# alertButton.net
KiCad netlist of a schematic drawn in Altium Designer
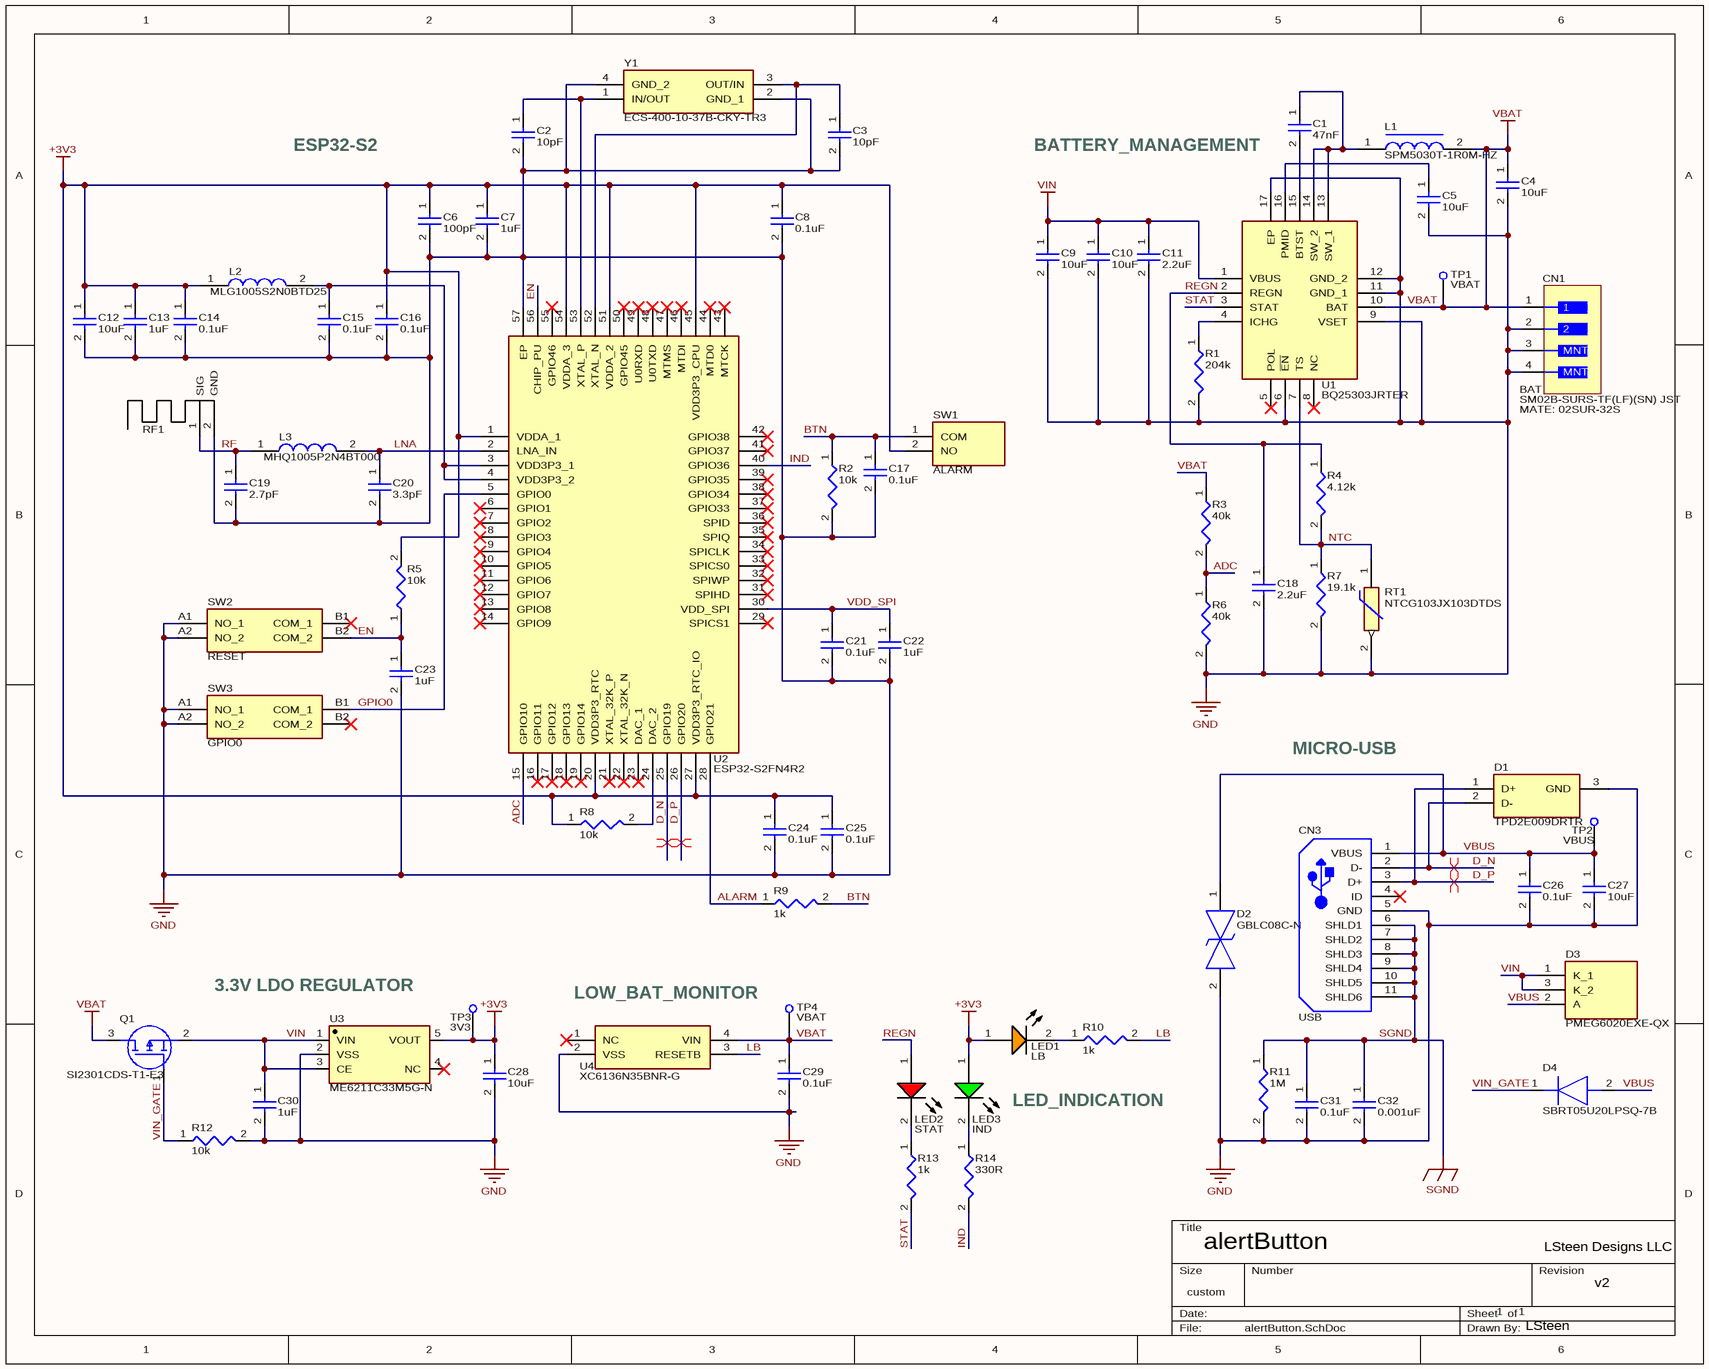
[diagram p0: alertButton.SchDoc]

(export (version "E")
  (design (tool "Eeschema 10.0.6"))
  (components
    (comp (ref "C1")
      (value "47nF")
      (footprint "SamacSys:CAPC1005X55N")
      (description "C0402")
      (libsource (lib "SamacSys") (part "C0402"))
    )
    (comp (ref "C2")
      (value "10pF")
      (footprint "SamacSys:CAPC1005X55N")
      (description "C0402")
      (libsource (lib "SamacSys") (part "C0402"))
    )
    (comp (ref "C3")
      (value "10pF")
      (footprint "SamacSys:CAPC1005X55N")
      (description "C0402")
      (libsource (lib "SamacSys") (part "C0402"))
    )
    (comp (ref "C4")
      (value "10uF")
      (footprint "SamacSys:CAPC1608X90N")
      (description "C0603")
      (libsource (lib "SamacSys") (part "C0603"))
    )
    (comp (ref "C5")
      (value "10uF")
      (footprint "SamacSys:CAPC1608X90N")
      (description "C0603")
      (libsource (lib "SamacSys") (part "C0603"))
    )
    (comp (ref "C6")
      (value "100pF")
      (footprint "SamacSys:CAPC1005X55N")
      (description "C0402")
      (libsource (lib "SamacSys") (part "C0402"))
    )
    (comp (ref "C7")
      (value "1uF")
      (footprint "SamacSys:CAPC1005X55N")
      (description "C0402")
      (libsource (lib "SamacSys") (part "C0402"))
    )
    (comp (ref "C8")
      (value "0.1uF")
      (footprint "SamacSys:CAPC1005X55N")
      (description "C0402")
      (libsource (lib "SamacSys") (part "C0402"))
    )
    (comp (ref "C9")
      (value "10uF")
      (footprint "SamacSys:CAPC1608X90N")
      (description "C0603")
      (libsource (lib "SamacSys") (part "C0603"))
    )
    (comp (ref "C10")
      (value "10uF")
      (footprint "SamacSys:CAPC1608X90N")
      (description "C0603")
      (libsource (lib "SamacSys") (part "C0603"))
    )
    (comp (ref "C11")
      (value "2.2uF")
      (footprint "SamacSys:CAPC1005X55N")
      (description "C0402")
      (libsource (lib "SamacSys") (part "C0402"))
    )
    (comp (ref "C12")
      (value "10uF")
      (footprint "SamacSys:CAPC2012X140N")
      (description "C0805")
      (libsource (lib "SamacSys") (part "C0805"))
    )
    (comp (ref "C13")
      (value "1uF")
      (footprint "SamacSys:CAPC1005X55N")
      (description "C0402")
      (libsource (lib "SamacSys") (part "C0402"))
    )
    (comp (ref "C14")
      (value "0.1uF")
      (footprint "SamacSys:CAPC1005X55N")
      (description "C0402")
      (libsource (lib "SamacSys") (part "C0402"))
    )
    (comp (ref "C15")
      (value "0.1uF")
      (footprint "SamacSys:CAPC1005X55N")
      (description "C0402")
      (libsource (lib "SamacSys") (part "C0402"))
    )
    (comp (ref "C16")
      (value "0.1uF")
      (footprint "SamacSys:CAPC1005X55N")
      (description "C0402")
      (libsource (lib "SamacSys") (part "C0402"))
    )
    (comp (ref "C17")
      (value "0.1uF")
      (footprint "SamacSys:CAPC1005X55N")
      (description "C0402")
      (libsource (lib "SamacSys") (part "C0402"))
    )
    (comp (ref "C18")
      (value "2.2uF")
      (footprint "SamacSys:CAPC1005X55N")
      (description "C0402")
      (libsource (lib "SamacSys") (part "C0402"))
    )
    (comp (ref "C19")
      (value "2.7pF")
      (footprint "SamacSys:CAPC1005X56N")
      (description "C0402")
      (fields
        (field (name "MANUFACTURER_PART_NUMBER") "04023U2R7BAT2A")
        (field (name "MOUSER PART NUMBER") "581-04023U2.7B")
      )
      (libsource (lib "SamacSys") (part "04023U2R7BAT2A"))
    )
    (comp (ref "C20")
      (value "3.3pF")
      (footprint "SamacSys:CAPC1005X56N")
      (description "C0402")
      (fields (field (name "MANUFACTURER_PART_NUMBER") "04023A3R3CAT2A"))
      (libsource (lib "SamacSys") (part "04023A3R3CAT2A"))
    )
    (comp (ref "C21")
      (value "0.1uF")
      (footprint "SamacSys:CAPC1005X55N")
      (description "C0402")
      (libsource (lib "SamacSys") (part "C0402"))
    )
    (comp (ref "C22")
      (value "1uF")
      (footprint "SamacSys:CAPC1005X55N")
      (description "C0402")
      (libsource (lib "SamacSys") (part "C0402"))
    )
    (comp (ref "C23")
      (value "1uF")
      (footprint "SamacSys:CAPC1005X55N")
      (description "C0402")
      (libsource (lib "SamacSys") (part "C0402"))
    )
    (comp (ref "C24")
      (value "0.1uF")
      (footprint "SamacSys:CAPC1005X55N")
      (description "C0402")
      (libsource (lib "SamacSys") (part "C0402"))
    )
    (comp (ref "C25")
      (value "0.1uF")
      (footprint "SamacSys:CAPC1005X55N")
      (description "C0402")
      (libsource (lib "SamacSys") (part "C0402"))
    )
    (comp (ref "C26")
      (value "0.1uF")
      (footprint "SamacSys:CAPC1005X55N")
      (description "C0402")
      (libsource (lib "SamacSys") (part "C0402"))
    )
    (comp (ref "C27")
      (value "10uF")
      (footprint "SamacSys:CAPC1608X90N")
      (description "C0603")
      (libsource (lib "SamacSys") (part "C0603"))
    )
    (comp (ref "C28")
      (value "10uF")
      (footprint "SamacSys:CAPC1608X90N")
      (description "C0603")
      (libsource (lib "SamacSys") (part "C0603"))
    )
    (comp (ref "C29")
      (value "0.1uF")
      (footprint "SamacSys:CAPC1005X55N")
      (description "C0402")
      (libsource (lib "") (part "C0402_1"))
    )
    (comp (ref "C30")
      (value "1uF")
      (footprint "SamacSys:CAPC1005X55N")
      (description "C0402")
      (libsource (lib "SamacSys") (part "C0402"))
    )
    (comp (ref "C31")
      (value "0.1uF")
      (footprint "SamacSys:CAPC1005X55N")
      (description "C0402")
      (libsource (lib "SamacSys") (part "C0402"))
    )
    (comp (ref "C32")
      (value "0.001uF")
      (footprint "SamacSys:CAPC1005X55N")
      (description "C0402")
      (libsource (lib "SamacSys") (part "C0402"))
    )
    (comp (ref "CN1")
      (value "BAT")
      (footprint "SM02B-SURS-TF(LF)(SN)")
      (description "Connector")
      (fields
        (field (name "MANUFACTURER_PART_NUMBER") "SM02B-SURS-TF(LF)(SN)")
        (field (name "MOUSER PART NUMBER") "306-SM02B-SURS-TF(LF)(SN)")
      )
      (libsource (lib "Schlib1") (part "SM02B-SURS-TF(LF)(SN)"))
    )
    (comp (ref "CN3")
      (value "USB")
      (footprint "105017-0001")
      (description "Micro USB Connector")
      (fields
        (field (name "MANUFACTURER_PART_NUMBER") "105017-0001")
        (field (name "MOUSER PART NUMBER") "538-105017-0001")
      )
      (libsource (lib "SamacSys") (part "105017-0001"))
    )
    (comp (ref "D1")
      (value "TPD2E009DRTR")
      (footprint "SamacSys:SOTFL35P100X50-3N")
      (description "Integrated Circuit")
      (fields (field (name "MOUSER PART NUMBER") "595-TPD2E009DRTR"))
      (libsource (lib "SamacSys") (part "TPD2E009DRTR"))
    )
    (comp (ref "D2")
      (value "GBLC08C-N")
      (footprint "SOD-323_L1.8-W1.3-LS2.5-BI")
      (description "ESD DIODE-BI_LCSC#C314256")
      (libsource (lib "Schlib1") (part "GBLC08C-N"))
    )
    (comp (ref "D3")
      (value "PMEG6020EXE-QX")
      (footprint "SamacSys:PMEG6020EXEQX")
      (description "Schottky Diode")
      (libsource (lib "SamacSys") (part "PMEG6020EXE-QX"))
    )
    (comp (ref "D4")
      (value "SBRT05U20LPSQ-7B")
      (footprint "SamacSys:SBRT05U20LPSQ7B")
      (description "Diode")
      (fields (field (name "MOUSER PART NUMBER") "621-SBRT05U20LPSQ-7B"))
      (libsource (lib "SamacSys") (part "SBRT05U20LPSQ-7B"))
    )
    (comp (ref "L1")
      (value "SPM5030T-1R0M-HZ")
      (footprint "SamacSys:SPM5030")
      (description "Inductor (FeSi Core)")
      (fields (field (name "MOUSER PART NUMBER") "810-SPM5030T-1R0M-HZ"))
      (libsource (lib "SamacSys") (part "SPM5030T-1R0M-HZ"))
    )
    (comp (ref "L2")
      (value "MLG1005S2N0BTD25")
      (footprint "SamacSys:MLG1005")
      (description "Inductor")
      (fields (field (name "MOUSER PART NUMBER") "810-MLG1005S2N0BTD25"))
      (libsource (lib "SamacSys") (part "MLG1005S2N0BTD25"))
    )
    (comp (ref "L3")
      (value "MHQ1005P2N4BT000")
      (footprint "SamacSys:MHQ1005")
      (description "Inductor")
      (libsource (lib "SamacSys") (part "MHQ1005P2N4BT000"))
    )
    (comp (ref "LED1")
      (value "LB")
      (footprint "SM0402OC")
      (description "LED ORANGE")
      (fields
        (field (name "MANUFACTURER_PART_NUMBER") "SM0402OC")
        (field (name "MOUSER PART NUMBER") "749-SM0402OC")
      )
      (libsource (lib "SamacSys") (part "SM0402OC"))
    )
    (comp (ref "LED2")
      (value "STAT")
      (footprint "SamacSys:SM0402RC")
      (description "LED RED")
      (fields
        (field (name "MANUFACTURER_PART_NUMBER") "SM0402RC")
        (field (name "MOUSER PART NUMBER") "749-SM0402RC")
      )
      (libsource (lib "SamacSys") (part "SM0402RC"))
    )
    (comp (ref "LED3")
      (value "IND")
      (footprint "SamacSys:SM0402GC")
      (description "LED GREEN")
      (fields
        (field (name "MANUFACTURER_PART_NUMBER") "SM0402GC")
        (field (name "MOUSER PART NUMBER") "749-SM0402GC")
      )
      (libsource (lib "SamacSys") (part "SM0402GC"))
    )
    (comp (ref "Q1")
      (value "SI2301CDS-T1-E3")
      (footprint "SamacSys:SOT95P237X112-3N")
      (description "MOSFET (P-Channel)")
      (fields (field (name "MOUSER PART NUMBER") "781-SI2301CDS-E3"))
      (libsource (lib "SamacSys") (part "SI2301CDS-T1-E3"))
    )
    (comp (ref "R1")
      (value "204k")
      (footprint "SamacSys:ERA2AED122X")
      (description "R0402")
      (libsource (lib "SamacSys") (part "R0402"))
    )
    (comp (ref "R2")
      (value "10k")
      (footprint "SamacSys:ERA2AED122X")
      (description "R0402")
      (libsource (lib "SamacSys") (part "R0402"))
    )
    (comp (ref "R3")
      (value "40k")
      (footprint "SamacSys:ERA2AED122X")
      (description "R0402")
      (libsource (lib "SamacSys") (part "R0402"))
    )
    (comp (ref "R4")
      (value "4.12k")
      (footprint "SamacSys:ERA2AED122X")
      (description "R0402")
      (libsource (lib "SamacSys") (part "R0402"))
    )
    (comp (ref "R5")
      (value "10k")
      (footprint "SamacSys:ERA2AED122X")
      (description "R0402")
      (libsource (lib "SamacSys") (part "R0402"))
    )
    (comp (ref "R6")
      (value "40k")
      (footprint "SamacSys:ERA2AED122X")
      (description "R0402")
      (libsource (lib "SamacSys") (part "R0402"))
    )
    (comp (ref "R7")
      (value "19.1k")
      (footprint "SamacSys:ERA2AED122X")
      (description "R0402")
      (libsource (lib "SamacSys") (part "R0402"))
    )
    (comp (ref "R8")
      (value "10k")
      (footprint "SamacSys:ERA2AED122X")
      (description "R0402")
      (libsource (lib "SamacSys") (part "R0402"))
    )
    (comp (ref "R9")
      (value "1k")
      (footprint "SamacSys:ERA2AED122X")
      (description "R0402")
      (libsource (lib "SamacSys") (part "R0402"))
    )
    (comp (ref "R10")
      (value "1k")
      (footprint "SamacSys:ERA2AED122X")
      (description "R0402")
      (libsource (lib "SamacSys") (part "R0402"))
    )
    (comp (ref "R11")
      (value "1M")
      (footprint "SamacSys:ERA2AED122X")
      (description "R0402")
      (libsource (lib "SamacSys") (part "R0402"))
    )
    (comp (ref "R12")
      (value "10k")
      (footprint "SamacSys:ERA2AED122X")
      (description "R0402")
      (libsource (lib "SamacSys") (part "R0402"))
    )
    (comp (ref "R13")
      (value "1k")
      (footprint "SamacSys:ERA2AED122X")
      (description "R0402")
      (libsource (lib "SamacSys") (part "R0402"))
    )
    (comp (ref "R14")
      (value "330R")
      (footprint "SamacSys:ERA2AED122X")
      (description "R0402")
      (libsource (lib "SamacSys") (part "R0402"))
    )
    (comp (ref "RF1") (value "Antenna") (footprint "SWRA117D") (libsource (lib "Schlib1") (part "Antenna")))
    (comp (ref "RT1")
      (value "NTCG103JX103DTDS")
      (footprint "SamacSys:THRMC1005X55N")
      (description "Thermistor")
      (fields (field (name "MOUSER PART NUMBER") "810-NTCG103JX103DTDS"))
      (libsource (lib "SamacSys") (part "NTCG103JX103DTDS"))
    )
    (comp (ref "SW1")
      (value "ALARM")
      (footprint "SamacSys:TS1088R02026")
      (description "Switch")
      (fields (field (name "MANUFACTURER_PART_NUMBER") "TS-1088R-02026"))
      (libsource (lib "SamacSys") (part "TS-1088R-02026"))
    )
    (comp (ref "SW2")
      (value "RESET")
      (footprint "SamacSys:EVPBB0AAB000")
      (description "Switch")
      (fields
        (field (name "MANUFACTURER_PART_NUMBER") "EVP-BB0AAB000")
        (field (name "MOUSER PART NUMBER") "667-EVP-BB0AAB000")
      )
      (libsource (lib "SamacSys") (part "EVP-BB0AAB000"))
    )
    (comp (ref "SW3")
      (value "GPIO0")
      (footprint "SamacSys:EVPBB0AAB000")
      (description "Switch")
      (fields
        (field (name "MANUFACTURER_PART_NUMBER") "EVP-BB0AAB000")
        (field (name "MOUSER PART NUMBER") "667-EVP-BB0AAB000")
      )
      (libsource (lib "SamacSys") (part "EVP-BB0AAB000"))
    )
    (comp (ref "TP1")
      (value "VBAT")
      (footprint "TP")
      (description "TestPoint")
      (libsource (lib "Schlib1") (part "TestPoint"))
    )
    (comp (ref "TP2")
      (value "VBUS")
      (footprint "TP")
      (description "TestPoint")
      (libsource (lib "Schlib1") (part "TestPoint"))
    )
    (comp (ref "TP3")
      (value "3V3")
      (footprint "TP")
      (description "TestPoint")
      (libsource (lib "Schlib1") (part "TestPoint"))
    )
    (comp (ref "TP4")
      (value "VBAT")
      (footprint "TP")
      (description "TestPoint")
      (libsource (lib "Schlib1") (part "TestPoint"))
    )
    (comp (ref "U1")
      (value "BQ25303JRTER")
      (footprint "SamacSys:QFN50P300X300X80-17N-D")
      (description "Integrated Circuit")
      (fields (field (name "MOUSER PART NUMBER") "595-BQ25303JRTER"))
      (libsource (lib "*") (part "BQ25303JRTER"))
    )
    (comp (ref "U2")
      (value "ESP32-S2FN4R2")
      (footprint "SamacSys:QFN40P700X700X90-57N-D")
      (description "Integrated Circuit")
      (fields (field (name "MOUSER PART NUMBER") "356-ESP32-S2FN4R2"))
      (libsource (lib "SamacSys") (part "ESP32-S2FN4R2"))
    )
    (comp (ref "U3")
      (value "ME6211C33M5G-N")
      (footprint "SOT95P270X145-5N")
      (description "LCSC +3.3V LDO 500mA VDIF=120mV@100mA")
      (libsource (lib "Schlib1") (part "ME6211C33M5G-N"))
    )
    (comp (ref "U4")
      (value "XC6136N35BNR-G")
      (footprint "SamacSys:XC6136C12ANRG")
      (description "Integrated Circuit")
      (fields (field (name "MOUSER PART NUMBER") "865-XC6136N35BNR-G"))
      (libsource (lib "SamacSys") (part "XC6136N35BNR-G"))
    )
    (comp (ref "Y1")
      (value "ECS-400-10-37B-CKY-TR3")
      (footprint "SamacSys:ECS4001037BCKYTR3")
      (description "Crystal or Oscillator")
      (fields (field (name "MOUSER PART NUMBER") "520-EC4001037BCKYTR3"))
      (libsource (lib "SamacSys") (part "ECS-400-10-37B-CKY-TR3"))
    )
  )
  (nets
    (net (code "1") (name "+3V3") (class "Default")
      (node (ref "C12") (pin "1") (pinfunction "1_1") (pintype "passive"))
      (node (ref "C13") (pin "1") (pinfunction "1_1") (pintype "passive"))
      (node (ref "C14") (pin "1") (pinfunction "1_1") (pintype "passive"))
      (node (ref "C16") (pin "1") (pinfunction "1_1") (pintype "passive"))
      (node (ref "C24") (pin "1") (pinfunction "1_1") (pintype "passive"))
      (node (ref "C25") (pin "1") (pinfunction "1_1") (pintype "passive"))
      (node (ref "C28") (pin "1") (pinfunction "1_1") (pintype "passive"))
      (node (ref "C6") (pin "1") (pinfunction "1_1") (pintype "passive"))
      (node (ref "C7") (pin "1") (pinfunction "1_1") (pintype "passive"))
      (node (ref "C8") (pin "1") (pinfunction "1_1") (pintype "passive"))
      (node (ref "L2") (pin "1") (pinfunction "1_1") (pintype "passive"))
      (node (ref "LED1") (pin "1") (pinfunction "A_1") (pintype "passive"))
      (node (ref "LED3") (pin "1") (pinfunction "A_1") (pintype "passive"))
      (node (ref "R5") (pin "2") (pinfunction "2_2") (pintype "passive"))
      (node (ref "R8") (pin "1") (pinfunction "1_1") (pintype "passive"))
      (node (ref "SW1") (pin "2") (pinfunction "NO_2") (pintype "passive"))
      (node (ref "TP3") (pin "1") (pinfunction "1_1") (pintype "passive"))
      (node (ref "U2") (pin "1") (pinfunction "VDDA_1_1") (pintype "passive"))
      (node (ref "U2") (pin "20") (pinfunction "VDD3P3_RTC_20") (pintype "passive"))
      (node (ref "U2") (pin "27") (pinfunction "VDD3P3_RTC_IO_27") (pintype "passive"))
      (node (ref "U2") (pin "45") (pinfunction "VDD3P3_CPU_45") (pintype "passive"))
      (node (ref "U2") (pin "51") (pinfunction "VDDA_2_51") (pintype "passive"))
      (node (ref "U2") (pin "54") (pinfunction "VDDA_3_54") (pintype "passive"))
      (node (ref "U3") (pin "5") (pinfunction "VOUT_5") (pintype "passive"))
    )
    (net (code "2") (name "/ADC") (class "Default")
      (node (ref "R3") (pin "2") (pinfunction "2_2") (pintype "passive"))
      (node (ref "R6") (pin "1") (pinfunction "1_1") (pintype "passive"))
      (node (ref "U2") (pin "15") (pinfunction "GPIO10_15") (pintype "passive"))
    )
    (net (code "3") (name "/ALARM") (class "Default")
      (node (ref "R9") (pin "1") (pinfunction "1_1") (pintype "passive"))
      (node (ref "U2") (pin "28") (pinfunction "GPIO21_28") (pintype "passive"))
    )
    (net (code "4") (name "/BTN") (class "Default")
      (node (ref "C17") (pin "1") (pinfunction "1_1") (pintype "passive"))
      (node (ref "R2") (pin "1") (pinfunction "1_1") (pintype "passive"))
      (node (ref "R9") (pin "2") (pinfunction "2_2") (pintype "passive"))
      (node (ref "SW1") (pin "1") (pinfunction "COM_1") (pintype "passive"))
    )
    (net (code "5") (name "/D_N") (class "Default")
      (node (ref "CN3") (pin "2") (pinfunction "D-_2") (pintype "passive"))
      (node (ref "D1") (pin "2") (pinfunction "D-_2") (pintype "passive"))
      (node (ref "U2") (pin "25") (pinfunction "GPIO19_25") (pintype "passive"))
    )
    (net (code "6") (name "/D_P") (class "Default")
      (node (ref "CN3") (pin "3") (pinfunction "D+_3") (pintype "passive"))
      (node (ref "D1") (pin "1") (pinfunction "D+_1") (pintype "passive"))
      (node (ref "U2") (pin "26") (pinfunction "GPIO20_26") (pintype "passive"))
    )
    (net (code "7") (name "/EN") (class "Default")
      (node (ref "C23") (pin "1") (pinfunction "1_1") (pintype "passive"))
      (node (ref "R5") (pin "1") (pinfunction "1_1") (pintype "passive"))
      (node (ref "SW2") (pin "B2") (pinfunction "COM_2_B2") (pintype "passive"))
      (node (ref "U2") (pin "56") (pinfunction "CHIP_PU_56") (pintype "passive"))
    )
    (net (code "8") (name "/GPIO0") (class "Default")
      (node (ref "SW3") (pin "B1") (pinfunction "COM_1_B1") (pintype "passive"))
      (node (ref "U2") (pin "5") (pinfunction "GPIO0_5") (pintype "passive"))
    )
    (net (code "9") (name "/IND") (class "Default")
      (node (ref "R14") (pin "2") (pinfunction "2_2") (pintype "passive"))
      (node (ref "U2") (pin "40") (pinfunction "GPIO36_40") (pintype "passive"))
    )
    (net (code "10") (name "/LB") (class "Default")
      (node (ref "R10") (pin "2") (pinfunction "2_2") (pintype "passive"))
      (node (ref "U4") (pin "3") (pinfunction "RESETB_3") (pintype "passive"))
    )
    (net (code "11") (name "/LNA") (class "Default")
      (node (ref "C20") (pin "1") (pinfunction "1_1") (pintype "passive"))
      (node (ref "L3") (pin "2") (pinfunction "2_2") (pintype "passive"))
      (node (ref "U2") (pin "2") (pinfunction "LNA_IN_2") (pintype "passive"))
    )
    (net (code "12") (name "/NTC") (class "Default")
      (node (ref "R4") (pin "2") (pinfunction "2_2") (pintype "passive"))
      (node (ref "R7") (pin "1") (pinfunction "1_1") (pintype "passive"))
      (node (ref "RT1") (pin "1") (pinfunction "1_1") (pintype "passive"))
      (node (ref "U1") (pin "7") (pinfunction "TS_7") (pintype "passive"))
    )
    (net (code "13") (name "/REGN") (class "Default")
      (node (ref "C18") (pin "1") (pinfunction "1_1") (pintype "passive"))
      (node (ref "LED2") (pin "1") (pinfunction "A_1") (pintype "passive"))
      (node (ref "R4") (pin "1") (pinfunction "1_1") (pintype "passive"))
      (node (ref "U1") (pin "2") (pinfunction "REGN_2") (pintype "passive"))
    )
    (net (code "14") (name "/RF") (class "Default")
      (node (ref "C19") (pin "1") (pinfunction "1_1") (pintype "passive"))
      (node (ref "L3") (pin "1") (pinfunction "1_1") (pintype "passive"))
      (node (ref "RF1") (pin "1") (pinfunction "SIG_1") (pintype "passive"))
    )
    (net (code "15") (name "/STAT") (class "Default")
      (node (ref "R13") (pin "2") (pinfunction "2_2") (pintype "passive"))
      (node (ref "U1") (pin "3") (pinfunction "STAT_3") (pintype "passive"))
    )
    (net (code "16") (name "/VBUS") (class "Default")
      (node (ref "C26") (pin "1") (pinfunction "1_1") (pintype "passive"))
      (node (ref "C27") (pin "1") (pinfunction "1_1") (pintype "passive"))
      (node (ref "CN3") (pin "1") (pinfunction "VBUS_1") (pintype "passive"))
      (node (ref "D2") (pin "1") (pinfunction "1_1") (pintype "passive"))
      (node (ref "D3") (pin "2") (pinfunction "A_2") (pintype "passive"))
      (node (ref "D4") (pin "2") (pinfunction "A_2") (pintype "passive"))
      (node (ref "TP2") (pin "1") (pinfunction "1_1") (pintype "passive"))
    )
    (net (code "17") (name "/VDD_SPI") (class "Default")
      (node (ref "C21") (pin "1") (pinfunction "1_1") (pintype "passive"))
      (node (ref "C22") (pin "1") (pinfunction "1_1") (pintype "passive"))
      (node (ref "U2") (pin "30") (pinfunction "VDD_SPI_30") (pintype "passive"))
    )
    (net (code "18") (name "/VIN_GATE") (class "Default")
      (node (ref "D4") (pin "1") (pinfunction "K_1") (pintype "passive"))
      (node (ref "Q1") (pin "1") (pinfunction "G_1") (pintype "passive"))
      (node (ref "R12") (pin "1") (pinfunction "1_1") (pintype "passive"))
    )
    (net (code "19") (name "GND") (class "Default")
      (node (ref "C10") (pin "2") (pinfunction "2_2") (pintype "passive"))
      (node (ref "C11") (pin "2") (pinfunction "2_2") (pintype "passive"))
      (node (ref "C12") (pin "2") (pinfunction "2_2") (pintype "passive"))
      (node (ref "C13") (pin "2") (pinfunction "2_2") (pintype "passive"))
      (node (ref "C14") (pin "2") (pinfunction "2_2") (pintype "passive"))
      (node (ref "C15") (pin "2") (pinfunction "2_2") (pintype "passive"))
      (node (ref "C16") (pin "2") (pinfunction "2_2") (pintype "passive"))
      (node (ref "C17") (pin "2") (pinfunction "2_2") (pintype "passive"))
      (node (ref "C18") (pin "2") (pinfunction "2_2") (pintype "passive"))
      (node (ref "C19") (pin "2") (pinfunction "2_2") (pintype "passive"))
      (node (ref "C2") (pin "2") (pinfunction "2_2") (pintype "passive"))
      (node (ref "C20") (pin "2") (pinfunction "2_2") (pintype "passive"))
      (node (ref "C21") (pin "2") (pinfunction "2_2") (pintype "passive"))
      (node (ref "C22") (pin "2") (pinfunction "2_2") (pintype "passive"))
      (node (ref "C23") (pin "2") (pinfunction "2_2") (pintype "passive"))
      (node (ref "C24") (pin "2") (pinfunction "2_2") (pintype "passive"))
      (node (ref "C25") (pin "2") (pinfunction "2_2") (pintype "passive"))
      (node (ref "C26") (pin "2") (pinfunction "2_2") (pintype "passive"))
      (node (ref "C27") (pin "2") (pinfunction "2_2") (pintype "passive"))
      (node (ref "C28") (pin "2") (pinfunction "2_2") (pintype "passive"))
      (node (ref "C29") (pin "2") (pinfunction "2_2") (pintype "passive"))
      (node (ref "C3") (pin "2") (pinfunction "2_2") (pintype "passive"))
      (node (ref "C30") (pin "2") (pinfunction "2_2") (pintype "passive"))
      (node (ref "C31") (pin "2") (pinfunction "2_2") (pintype "passive"))
      (node (ref "C32") (pin "2") (pinfunction "2_2") (pintype "passive"))
      (node (ref "C4") (pin "2") (pinfunction "2_2") (pintype "passive"))
      (node (ref "C5") (pin "2") (pinfunction "2_2") (pintype "passive"))
      (node (ref "C6") (pin "2") (pinfunction "2_2") (pintype "passive"))
      (node (ref "C7") (pin "2") (pinfunction "2_2") (pintype "passive"))
      (node (ref "C8") (pin "2") (pinfunction "2_2") (pintype "passive"))
      (node (ref "C9") (pin "2") (pinfunction "2_2") (pintype "passive"))
      (node (ref "CN1") (pin "2") (pinfunction "2_2") (pintype "passive"))
      (node (ref "CN1") (pin "3") (pinfunction "MNT_3") (pintype "passive"))
      (node (ref "CN1") (pin "4") (pinfunction "MNT_4") (pintype "passive"))
      (node (ref "CN3") (pin "5") (pinfunction "GND_5") (pintype "passive"))
      (node (ref "D1") (pin "3") (pinfunction "GND_3") (pintype "passive"))
      (node (ref "D2") (pin "2") (pinfunction "2_2") (pintype "passive"))
      (node (ref "R1") (pin "2") (pinfunction "2_2") (pintype "passive"))
      (node (ref "R11") (pin "2") (pinfunction "2_2") (pintype "passive"))
      (node (ref "R12") (pin "2") (pinfunction "2_2") (pintype "passive"))
      (node (ref "R2") (pin "2") (pinfunction "2_2") (pintype "passive"))
      (node (ref "R6") (pin "2") (pinfunction "2_2") (pintype "passive"))
      (node (ref "R7") (pin "2") (pinfunction "2_2") (pintype "passive"))
      (node (ref "RF1") (pin "2") (pinfunction "GND_2") (pintype "passive"))
      (node (ref "RT1") (pin "2") (pinfunction "2_2") (pintype "output"))
      (node (ref "SW2") (pin "A1") (pinfunction "NO_1_A1") (pintype "passive"))
      (node (ref "SW2") (pin "A2") (pinfunction "NO_2_A2") (pintype "passive"))
      (node (ref "SW3") (pin "A1") (pinfunction "NO_1_A1") (pintype "passive"))
      (node (ref "SW3") (pin "A2") (pinfunction "NO_2_A2") (pintype "passive"))
      (node (ref "U1") (pin "11") (pinfunction "GND_1_11") (pintype "passive"))
      (node (ref "U1") (pin "12") (pinfunction "GND_2_12") (pintype "passive"))
      (node (ref "U1") (pin "17") (pinfunction "EP_17") (pintype "passive"))
      (node (ref "U1") (pin "6") (pinfunction "~{EN}_6") (pintype "passive"))
      (node (ref "U1") (pin "9") (pinfunction "VSET_9") (pintype "passive"))
      (node (ref "U2") (pin "57") (pinfunction "EP_57") (pintype "passive"))
      (node (ref "U3") (pin "2") (pinfunction "VSS_2") (pintype "passive"))
      (node (ref "U4") (pin "2") (pinfunction "VSS_2") (pintype "passive"))
      (node (ref "Y1") (pin "2") (pinfunction "GND_1_2") (pintype "passive"))
      (node (ref "Y1") (pin "4") (pinfunction "GND_2_4") (pintype "passive"))
    )
    (net (code "20") (name "Net-(LED1-K)") (class "Default")
      (node (ref "LED1") (pin "2") (pinfunction "K_2") (pintype "passive"))
      (node (ref "R10") (pin "1") (pinfunction "1_1") (pintype "passive"))
    )
    (net (code "21") (name "Net-(LED2-K)") (class "Default")
      (node (ref "LED2") (pin "2") (pinfunction "K_2") (pintype "passive"))
      (node (ref "R13") (pin "1") (pinfunction "1_1") (pintype "passive"))
    )
    (net (code "22") (name "Net-(LED3-K)") (class "Default")
      (node (ref "LED3") (pin "2") (pinfunction "K_2") (pintype "passive"))
      (node (ref "R14") (pin "1") (pinfunction "1_1") (pintype "passive"))
    )
    (net (code "23") (name "Net-(U1-BTST)") (class "Default")
      (node (ref "C1") (pin "2") (pinfunction "2_2") (pintype "passive"))
      (node (ref "U1") (pin "15") (pinfunction "BTST_15") (pintype "passive"))
    )
    (net (code "24") (name "Net-(U1-ICHG)") (class "Default")
      (node (ref "R1") (pin "1") (pinfunction "1_1") (pintype "passive"))
      (node (ref "U1") (pin "4") (pinfunction "ICHG_4") (pintype "passive"))
    )
    (net (code "25") (name "Net-(U1-PMID)") (class "Default")
      (node (ref "C5") (pin "1") (pinfunction "1_1") (pintype "passive"))
      (node (ref "U1") (pin "16") (pinfunction "PMID_16") (pintype "passive"))
    )
    (net (code "26") (name "Net-(U1-SW_1)") (class "Default")
      (node (ref "C1") (pin "1") (pinfunction "1_1") (pintype "passive"))
      (node (ref "L1") (pin "1") (pinfunction "1_1") (pintype "passive"))
      (node (ref "U1") (pin "13") (pinfunction "SW_1_13") (pintype "passive"))
      (node (ref "U1") (pin "14") (pinfunction "SW_2_14") (pintype "passive"))
    )
    (net (code "27") (name "Net-(U2-DAC_2)") (class "Default")
      (node (ref "R8") (pin "2") (pinfunction "2_2") (pintype "passive"))
      (node (ref "U2") (pin "24") (pinfunction "DAC_2_24") (pintype "passive"))
    )
    (net (code "28") (name "Net-(U2-VDD3P3_1)") (class "Default")
      (node (ref "C15") (pin "1") (pinfunction "1_1") (pintype "passive"))
      (node (ref "L2") (pin "2") (pinfunction "2_2") (pintype "passive"))
      (node (ref "U2") (pin "3") (pinfunction "VDD3P3_1_3") (pintype "passive"))
      (node (ref "U2") (pin "4") (pinfunction "VDD3P3_2_4") (pintype "passive"))
    )
    (net (code "29") (name "Net-(U2-XTAL_N)") (class "Default")
      (node (ref "C3") (pin "1") (pinfunction "1_1") (pintype "passive"))
      (node (ref "U2") (pin "52") (pinfunction "XTAL_N_52") (pintype "passive"))
      (node (ref "Y1") (pin "3") (pinfunction "OUT/IN_3") (pintype "passive"))
    )
    (net (code "30") (name "Net-(U2-XTAL_P)") (class "Default")
      (node (ref "C2") (pin "1") (pinfunction "1_1") (pintype "passive"))
      (node (ref "U2") (pin "53") (pinfunction "XTAL_P_53") (pintype "passive"))
      (node (ref "Y1") (pin "1") (pinfunction "IN/OUT_1") (pintype "passive"))
    )
    (net (code "31") (name "SGND") (class "Default")
      (node (ref "C31") (pin "1") (pinfunction "1_1") (pintype "passive"))
      (node (ref "C32") (pin "1") (pinfunction "1_1") (pintype "passive"))
      (node (ref "CN3") (pin "10") (pinfunction "SHLD5_10") (pintype "passive"))
      (node (ref "CN3") (pin "11") (pinfunction "SHLD6_11") (pintype "passive"))
      (node (ref "CN3") (pin "6") (pinfunction "SHLD1_6") (pintype "passive"))
      (node (ref "CN3") (pin "7") (pinfunction "SHLD2_7") (pintype "passive"))
      (node (ref "CN3") (pin "8") (pinfunction "SHLD3_8") (pintype "passive"))
      (node (ref "CN3") (pin "9") (pinfunction "SHLD4_9") (pintype "passive"))
      (node (ref "R11") (pin "1") (pinfunction "1_1") (pintype "passive"))
    )
    (net (code "32") (name "VBAT") (class "Default")
      (node (ref "C29") (pin "1") (pinfunction "1_1") (pintype "passive"))
      (node (ref "C4") (pin "1") (pinfunction "1_1") (pintype "passive"))
      (node (ref "CN1") (pin "1") (pinfunction "1_1") (pintype "passive"))
      (node (ref "L1") (pin "2") (pinfunction "2_2") (pintype "passive"))
      (node (ref "Q1") (pin "3") (pinfunction "D_3") (pintype "passive"))
      (node (ref "R3") (pin "1") (pinfunction "1_1") (pintype "passive"))
      (node (ref "TP1") (pin "1") (pinfunction "1_1") (pintype "passive"))
      (node (ref "TP4") (pin "1") (pinfunction "1_1") (pintype "passive"))
      (node (ref "U1") (pin "10") (pinfunction "BAT_10") (pintype "passive"))
      (node (ref "U4") (pin "4") (pinfunction "VIN_4") (pintype "passive"))
    )
    (net (code "33") (name "VIN") (class "Default")
      (node (ref "C10") (pin "1") (pinfunction "1_1") (pintype "passive"))
      (node (ref "C11") (pin "1") (pinfunction "1_1") (pintype "passive"))
      (node (ref "C30") (pin "1") (pinfunction "1_1") (pintype "passive"))
      (node (ref "C9") (pin "1") (pinfunction "1_1") (pintype "passive"))
      (node (ref "D3") (pin "1") (pinfunction "K_1_1") (pintype "passive"))
      (node (ref "D3") (pin "3") (pinfunction "K_2_3") (pintype "passive"))
      (node (ref "Q1") (pin "2") (pinfunction "S_2") (pintype "passive"))
      (node (ref "U1") (pin "1") (pinfunction "VBUS_1") (pintype "passive"))
      (node (ref "U3") (pin "1") (pinfunction "VIN_1") (pintype "passive"))
      (node (ref "U3") (pin "3") (pinfunction "CE_3") (pintype "passive"))
    )
    (net (code "34") (name "unconnected-(CN3-ID-Pad4)") (class "Default")
      (node (ref "CN3") (pin "4") (pinfunction "ID_4") (pintype "passive+no_connect"))
    )
    (net (code "35") (name "unconnected-(SW2-COM_1-PadB1)") (class "Default")
      (node (ref "SW2") (pin "B1") (pinfunction "COM_1_B1") (pintype "passive+no_connect"))
    )
    (net (code "36") (name "unconnected-(SW3-COM_2-PadB2)") (class "Default")
      (node (ref "SW3") (pin "B2") (pinfunction "COM_2_B2") (pintype "passive+no_connect"))
    )
    (net (code "37") (name "unconnected-(U1-NC-Pad8)") (class "Default")
      (node (ref "U1") (pin "8") (pinfunction "NC_8") (pintype "passive+no_connect"))
    )
    (net (code "38") (name "unconnected-(U1-POL-Pad5)") (class "Default")
      (node (ref "U1") (pin "5") (pinfunction "POL_5") (pintype "passive+no_connect"))
    )
    (net (code "39") (name "unconnected-(U2-DAC_1-Pad23)") (class "Default")
      (node (ref "U2") (pin "23") (pinfunction "DAC_1_23") (pintype "passive+no_connect"))
    )
    (net (code "40") (name "unconnected-(U2-GPIO1-Pad6)") (class "Default")
      (node (ref "U2") (pin "6") (pinfunction "GPIO1_6") (pintype "passive+no_connect"))
    )
    (net (code "41") (name "unconnected-(U2-GPIO2-Pad7)") (class "Default")
      (node (ref "U2") (pin "7") (pinfunction "GPIO2_7") (pintype "passive+no_connect"))
    )
    (net (code "42") (name "unconnected-(U2-GPIO3-Pad8)") (class "Default")
      (node (ref "U2") (pin "8") (pinfunction "GPIO3_8") (pintype "passive+no_connect"))
    )
    (net (code "43") (name "unconnected-(U2-GPIO4-Pad9)") (class "Default")
      (node (ref "U2") (pin "9") (pinfunction "GPIO4_9") (pintype "passive+no_connect"))
    )
    (net (code "44") (name "unconnected-(U2-GPIO5-Pad10)") (class "Default")
      (node (ref "U2") (pin "10") (pinfunction "GPIO5_10") (pintype "passive+no_connect"))
    )
    (net (code "45") (name "unconnected-(U2-GPIO6-Pad11)") (class "Default")
      (node (ref "U2") (pin "11") (pinfunction "GPIO6_11") (pintype "passive+no_connect"))
    )
    (net (code "46") (name "unconnected-(U2-GPIO7-Pad12)") (class "Default")
      (node (ref "U2") (pin "12") (pinfunction "GPIO7_12") (pintype "passive+no_connect"))
    )
    (net (code "47") (name "unconnected-(U2-GPIO8-Pad13)") (class "Default")
      (node (ref "U2") (pin "13") (pinfunction "GPIO8_13") (pintype "passive+no_connect"))
    )
    (net (code "48") (name "unconnected-(U2-GPIO9-Pad14)") (class "Default")
      (node (ref "U2") (pin "14") (pinfunction "GPIO9_14") (pintype "passive+no_connect"))
    )
    (net (code "49") (name "unconnected-(U2-GPIO11-Pad16)") (class "Default")
      (node (ref "U2") (pin "16") (pinfunction "GPIO11_16") (pintype "passive+no_connect"))
    )
    (net (code "50") (name "unconnected-(U2-GPIO12-Pad17)") (class "Default")
      (node (ref "U2") (pin "17") (pinfunction "GPIO12_17") (pintype "passive+no_connect"))
    )
    (net (code "51") (name "unconnected-(U2-GPIO13-Pad18)") (class "Default")
      (node (ref "U2") (pin "18") (pinfunction "GPIO13_18") (pintype "passive+no_connect"))
    )
    (net (code "52") (name "unconnected-(U2-GPIO14-Pad19)") (class "Default")
      (node (ref "U2") (pin "19") (pinfunction "GPIO14_19") (pintype "passive+no_connect"))
    )
    (net (code "53") (name "unconnected-(U2-GPIO33-Pad37)") (class "Default")
      (node (ref "U2") (pin "37") (pinfunction "GPIO33_37") (pintype "passive+no_connect"))
    )
    (net (code "54") (name "unconnected-(U2-GPIO34-Pad38)") (class "Default")
      (node (ref "U2") (pin "38") (pinfunction "GPIO34_38") (pintype "passive+no_connect"))
    )
    (net (code "55") (name "unconnected-(U2-GPIO35-Pad39)") (class "Default")
      (node (ref "U2") (pin "39") (pinfunction "GPIO35_39") (pintype "passive+no_connect"))
    )
    (net (code "56") (name "unconnected-(U2-GPIO37-Pad41)") (class "Default")
      (node (ref "U2") (pin "41") (pinfunction "GPIO37_41") (pintype "passive+no_connect"))
    )
    (net (code "57") (name "unconnected-(U2-GPIO38-Pad42)") (class "Default")
      (node (ref "U2") (pin "42") (pinfunction "GPIO38_42") (pintype "passive+no_connect"))
    )
    (net (code "58") (name "unconnected-(U2-GPIO45-Pad50)") (class "Default")
      (node (ref "U2") (pin "50") (pinfunction "GPIO45_50") (pintype "passive+no_connect"))
    )
    (net (code "59") (name "unconnected-(U2-GPIO46-Pad55)") (class "Default")
      (node (ref "U2") (pin "55") (pinfunction "GPIO46_55") (pintype "passive+no_connect"))
    )
    (net (code "60") (name "unconnected-(U2-MTCK-Pad43)") (class "Default")
      (node (ref "U2") (pin "43") (pinfunction "MTCK_43") (pintype "passive+no_connect"))
    )
    (net (code "61") (name "unconnected-(U2-MTD0-Pad44)") (class "Default")
      (node (ref "U2") (pin "44") (pinfunction "MTD0_44") (pintype "passive+no_connect"))
    )
    (net (code "62") (name "unconnected-(U2-MTDI-Pad46)") (class "Default")
      (node (ref "U2") (pin "46") (pinfunction "MTDI_46") (pintype "passive+no_connect"))
    )
    (net (code "63") (name "unconnected-(U2-MTMS-Pad47)") (class "Default")
      (node (ref "U2") (pin "47") (pinfunction "MTMS_47") (pintype "passive+no_connect"))
    )
    (net (code "64") (name "unconnected-(U2-SPICLK-Pad34)") (class "Default")
      (node (ref "U2") (pin "34") (pinfunction "SPICLK_34") (pintype "passive+no_connect"))
    )
    (net (code "65") (name "unconnected-(U2-SPICS0-Pad33)") (class "Default")
      (node (ref "U2") (pin "33") (pinfunction "SPICS0_33") (pintype "passive+no_connect"))
    )
    (net (code "66") (name "unconnected-(U2-SPICS1-Pad29)") (class "Default")
      (node (ref "U2") (pin "29") (pinfunction "SPICS1_29") (pintype "passive+no_connect"))
    )
    (net (code "67") (name "unconnected-(U2-SPID-Pad36)") (class "Default")
      (node (ref "U2") (pin "36") (pinfunction "SPID_36") (pintype "passive+no_connect"))
    )
    (net (code "68") (name "unconnected-(U2-SPIHD-Pad31)") (class "Default")
      (node (ref "U2") (pin "31") (pinfunction "SPIHD_31") (pintype "passive+no_connect"))
    )
    (net (code "69") (name "unconnected-(U2-SPIQ-Pad35)") (class "Default")
      (node (ref "U2") (pin "35") (pinfunction "SPIQ_35") (pintype "passive+no_connect"))
    )
    (net (code "70") (name "unconnected-(U2-SPIWP-Pad32)") (class "Default")
      (node (ref "U2") (pin "32") (pinfunction "SPIWP_32") (pintype "passive+no_connect"))
    )
    (net (code "71") (name "unconnected-(U2-U0RXD-Pad49)") (class "Default")
      (node (ref "U2") (pin "49") (pinfunction "U0RXD_49") (pintype "passive+no_connect"))
    )
    (net (code "72") (name "unconnected-(U2-U0TXD-Pad48)") (class "Default")
      (node (ref "U2") (pin "48") (pinfunction "U0TXD_48") (pintype "passive+no_connect"))
    )
    (net (code "73") (name "unconnected-(U2-XTAL_32K_N-Pad22)") (class "Default")
      (node (ref "U2") (pin "22") (pinfunction "XTAL_32K_N_22") (pintype "passive+no_connect"))
    )
    (net (code "74") (name "unconnected-(U2-XTAL_32K_P-Pad21)") (class "Default")
      (node (ref "U2") (pin "21") (pinfunction "XTAL_32K_P_21") (pintype "passive+no_connect"))
    )
    (net (code "75") (name "unconnected-(U3-NC-Pad4)") (class "Default")
      (node (ref "U3") (pin "4") (pinfunction "NC_4") (pintype "passive+no_connect"))
    )
    (net (code "76") (name "unconnected-(U4-NC-Pad1)") (class "Default")
      (node (ref "U4") (pin "1") (pinfunction "NC_1") (pintype "passive+no_connect"))
    )
  )
)
